# FPGA_A.net
KiCad netlist of a schematic drawn in Altium Designer
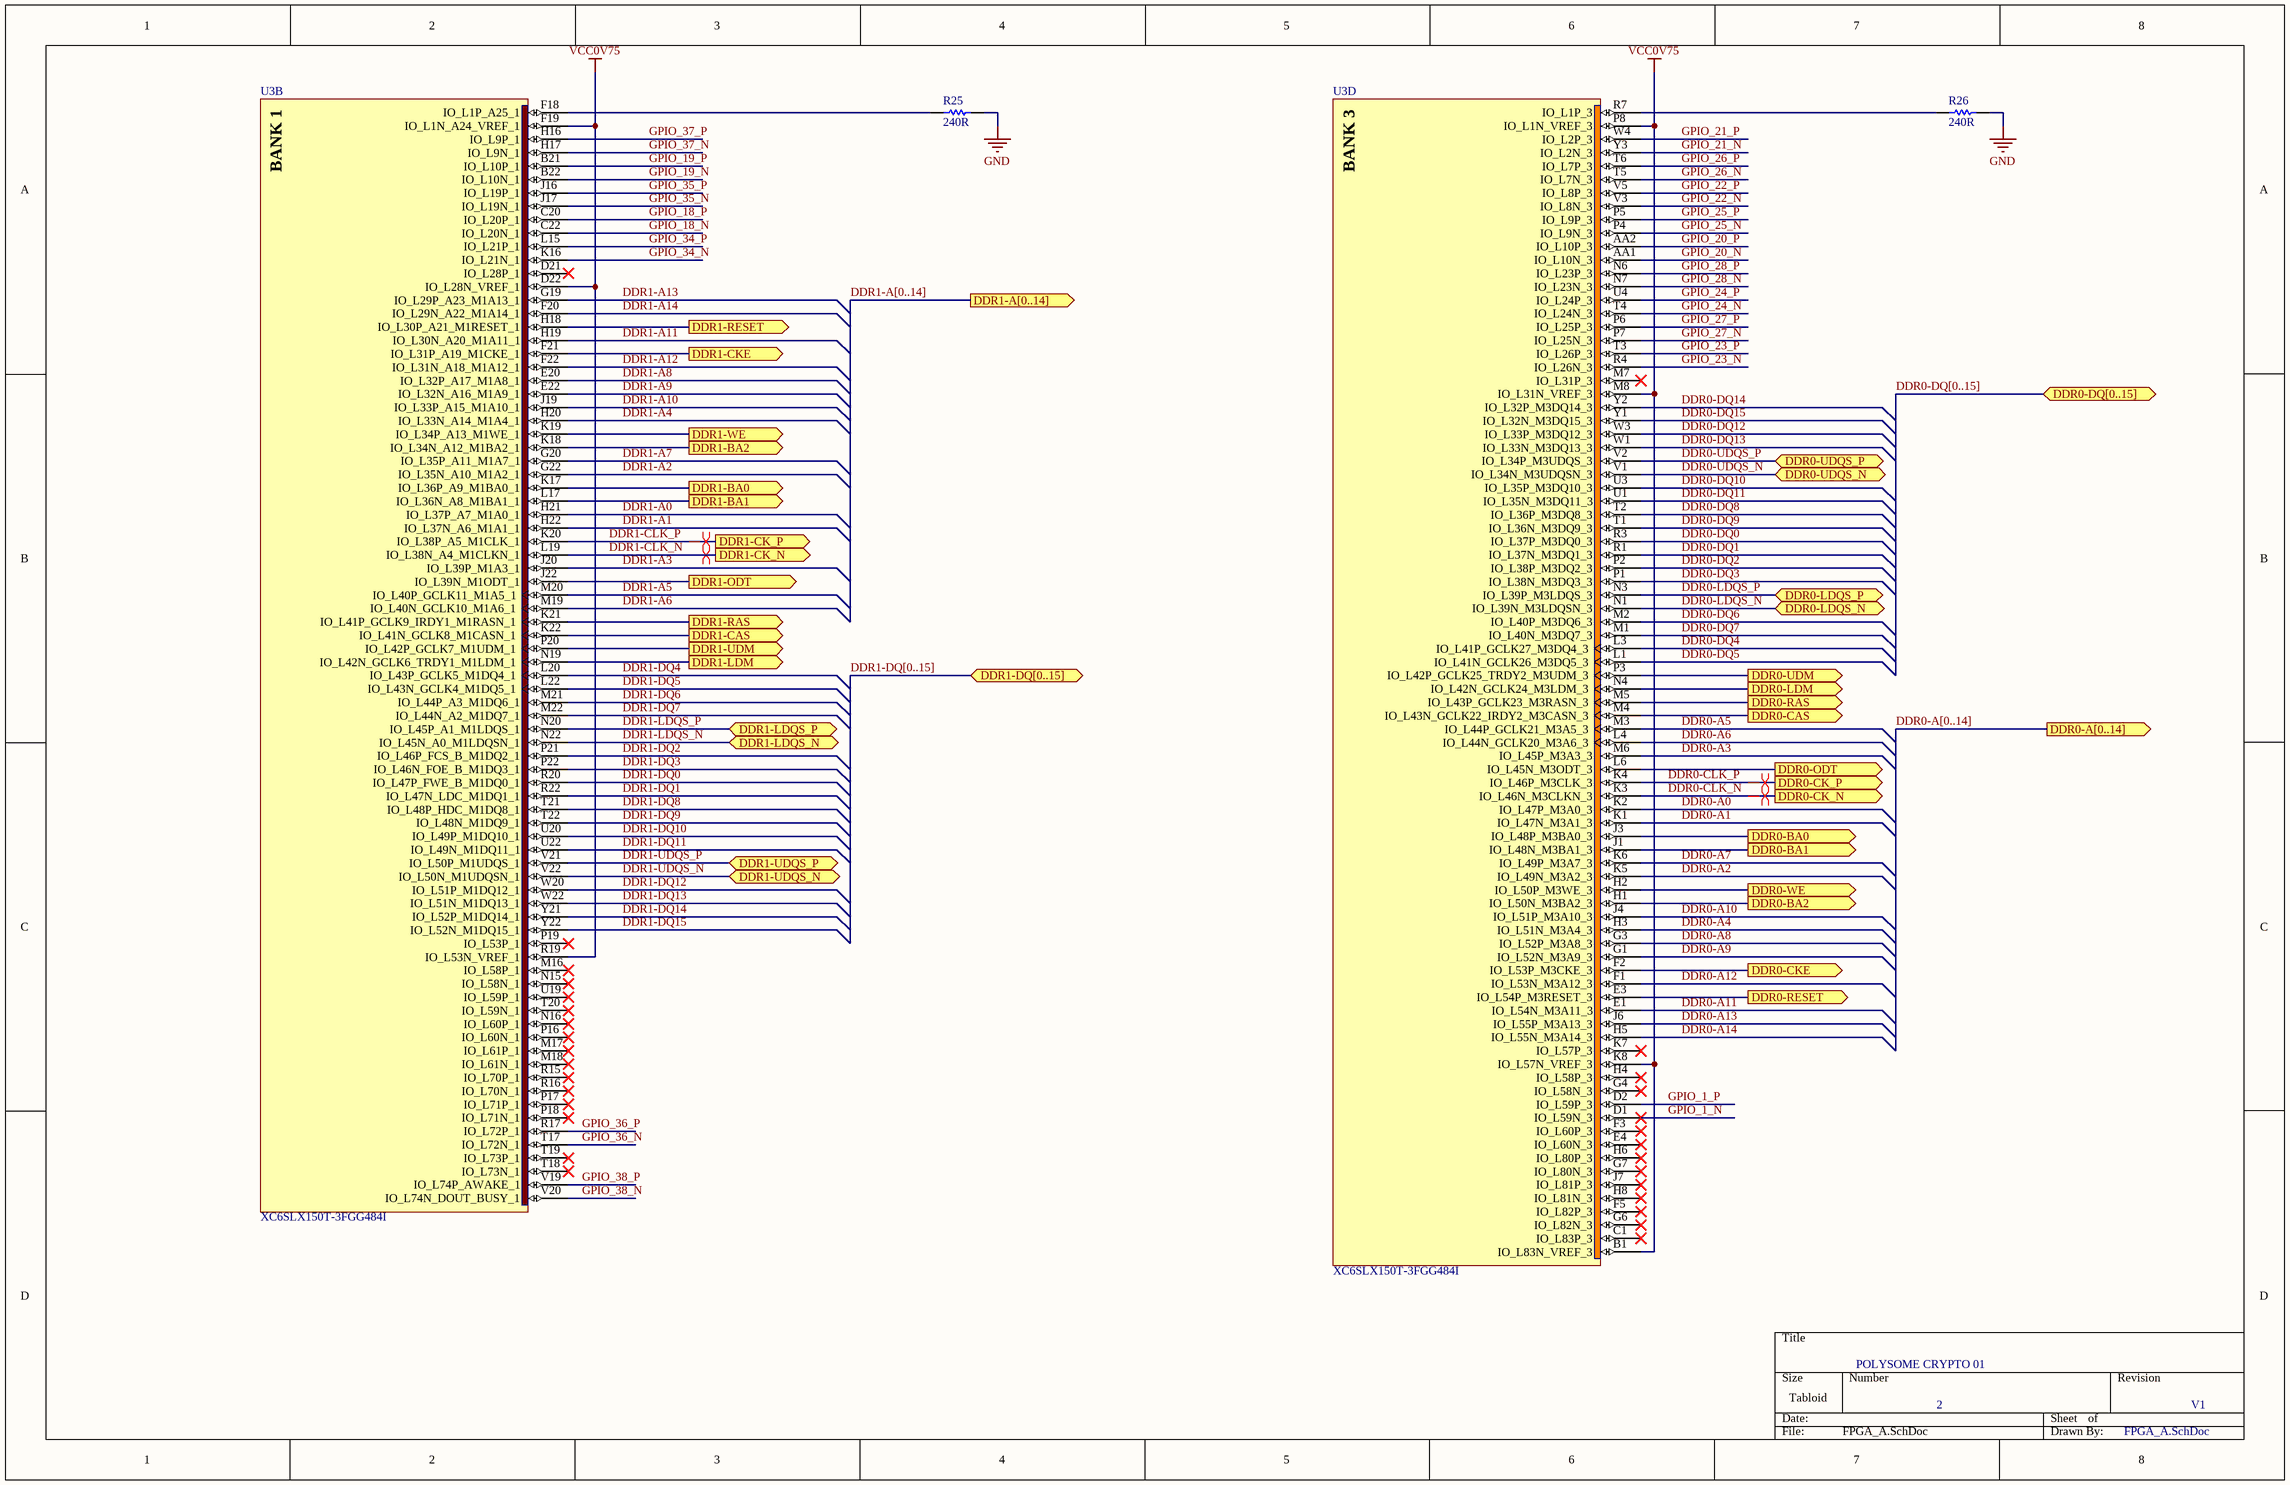
[diagram p0: FPGA_A.SchDoc]

(export (version "E")
  (design (tool "Eeschema 10.0.6"))
  (components
    (comp (ref "R25")
      (value "240R")
      (footprint "0402")
      (description "Semiconductor Resistor")
      (fields (field (name "Comment") "Res Semi") (field (name "PUBLISHER") "Altium Limited"))
      (libsource (lib "Miscellaneous Devices") (part "Res Semi"))
    )
    (comp (ref "R26")
      (value "240R")
      (footprint "0402")
      (description "Semiconductor Resistor")
      (fields (field (name "Comment") "Res Semi") (field (name "PUBLISHER") "Altium Limited"))
      (libsource (lib "Miscellaneous Devices") (part "Res Semi"))
    )
    (comp (ref "U3")
      (value "XC6SLX150T-3FGG484I")
      (footprint "FGG484")
      (fields (field (name "PUBLISHER") "Altium Limited"))
      (libsource (lib "Xilinx Spartan-6") (part "XC6SLX150T-3FGG484I"))
    )
  )
  (nets
    (net (code "1") (name "/DDR0-A0") (class "Default")
      (node (ref "U3") (pin "K2") (pinfunction "IO_L47P_M3A0_3_K2") (pintype "bidirectional"))
    )
    (net (code "2") (name "/DDR0-A1") (class "Default")
      (node (ref "U3") (pin "K1") (pinfunction "IO_L47N_M3A1_3_K1") (pintype "bidirectional"))
    )
    (net (code "3") (name "/DDR0-A2") (class "Default")
      (node (ref "U3") (pin "K5") (pinfunction "IO_L49N_M3A2_3_K5") (pintype "bidirectional"))
    )
    (net (code "4") (name "/DDR0-A3") (class "Default")
      (node (ref "U3") (pin "M6") (pinfunction "IO_L45P_M3A3_3_M6") (pintype "bidirectional"))
    )
    (net (code "5") (name "/DDR0-A4") (class "Default")
      (node (ref "U3") (pin "H3") (pinfunction "IO_L51N_M3A4_3_H3") (pintype "bidirectional"))
    )
    (net (code "6") (name "/DDR0-A5") (class "Default")
      (node (ref "U3") (pin "M3") (pinfunction "IO_L44P_GCLK21_M3A5_3_M3") (pintype "bidirectional"))
    )
    (net (code "7") (name "/DDR0-A6") (class "Default")
      (node (ref "U3") (pin "L4") (pinfunction "IO_L44N_GCLK20_M3A6_3_L4") (pintype "bidirectional"))
    )
    (net (code "8") (name "/DDR0-A7") (class "Default")
      (node (ref "U3") (pin "K6") (pinfunction "IO_L49P_M3A7_3_K6") (pintype "bidirectional"))
    )
    (net (code "9") (name "/DDR0-A8") (class "Default")
      (node (ref "U3") (pin "G3") (pinfunction "IO_L52P_M3A8_3_G3") (pintype "bidirectional"))
    )
    (net (code "10") (name "/DDR0-A9") (class "Default")
      (node (ref "U3") (pin "G1") (pinfunction "IO_L52N_M3A9_3_G1") (pintype "bidirectional"))
    )
    (net (code "11") (name "/DDR0-A10") (class "Default")
      (node (ref "U3") (pin "J4") (pinfunction "IO_L51P_M3A10_3_J4") (pintype "bidirectional"))
    )
    (net (code "12") (name "/DDR0-A11") (class "Default")
      (node (ref "U3") (pin "E1") (pinfunction "IO_L54N_M3A11_3_E1") (pintype "bidirectional"))
    )
    (net (code "13") (name "/DDR0-A12") (class "Default")
      (node (ref "U3") (pin "F1") (pinfunction "IO_L53N_M3A12_3_F1") (pintype "bidirectional"))
    )
    (net (code "14") (name "/DDR0-A13") (class "Default")
      (node (ref "U3") (pin "J6") (pinfunction "IO_L55P_M3A13_3_J6") (pintype "bidirectional"))
    )
    (net (code "15") (name "/DDR0-A14") (class "Default")
      (node (ref "U3") (pin "H5") (pinfunction "IO_L55N_M3A14_3_H5") (pintype "bidirectional"))
    )
    (net (code "17") (name "/DDR0-BA0") (class "Default")
      (node (ref "U3") (pin "J3") (pinfunction "IO_L48P_M3BA0_3_J3") (pintype "bidirectional"))
    )
    (net (code "18") (name "/DDR0-BA1") (class "Default")
      (node (ref "U3") (pin "J1") (pinfunction "IO_L48N_M3BA1_3_J1") (pintype "bidirectional"))
    )
    (net (code "19") (name "/DDR0-BA2") (class "Default")
      (node (ref "U3") (pin "H1") (pinfunction "IO_L50N_M3BA2_3_H1") (pintype "bidirectional"))
    )
    (net (code "20") (name "/DDR0-CAS") (class "Default")
      (node (ref "U3") (pin "M4") (pinfunction "IO_L43N_GCLK22_IRDY2_M3CASN_3_M4") (pintype "bidirectional"))
    )
    (net (code "21") (name "/DDR0-CKE") (class "Default")
      (node (ref "U3") (pin "F2") (pinfunction "IO_L53P_M3CKE_3_F2") (pintype "bidirectional"))
    )
    (net (code "22") (name "/DDR0-CLK_N") (class "Default")
      (node (ref "U3") (pin "K3") (pinfunction "IO_L46N_M3CLKN_3_K3") (pintype "bidirectional"))
    )
    (net (code "23") (name "/DDR0-CLK_P") (class "Default")
      (node (ref "U3") (pin "K4") (pinfunction "IO_L46P_M3CLK_3_K4") (pintype "bidirectional"))
    )
    (net (code "24") (name "/DDR0-DQ0") (class "Default")
      (node (ref "U3") (pin "R3") (pinfunction "IO_L37P_M3DQ0_3_R3") (pintype "bidirectional"))
    )
    (net (code "25") (name "/DDR0-DQ1") (class "Default")
      (node (ref "U3") (pin "R1") (pinfunction "IO_L37N_M3DQ1_3_R1") (pintype "bidirectional"))
    )
    (net (code "26") (name "/DDR0-DQ2") (class "Default")
      (node (ref "U3") (pin "P2") (pinfunction "IO_L38P_M3DQ2_3_P2") (pintype "bidirectional"))
    )
    (net (code "27") (name "/DDR0-DQ3") (class "Default")
      (node (ref "U3") (pin "P1") (pinfunction "IO_L38N_M3DQ3_3_P1") (pintype "bidirectional"))
    )
    (net (code "28") (name "/DDR0-DQ4") (class "Default")
      (node (ref "U3") (pin "L3") (pinfunction "IO_L41P_GCLK27_M3DQ4_3_L3") (pintype "bidirectional"))
    )
    (net (code "29") (name "/DDR0-DQ5") (class "Default")
      (node (ref "U3") (pin "L1") (pinfunction "IO_L41N_GCLK26_M3DQ5_3_L1") (pintype "bidirectional"))
    )
    (net (code "30") (name "/DDR0-DQ6") (class "Default")
      (node (ref "U3") (pin "M2") (pinfunction "IO_L40P_M3DQ6_3_M2") (pintype "bidirectional"))
    )
    (net (code "31") (name "/DDR0-DQ7") (class "Default")
      (node (ref "U3") (pin "M1") (pinfunction "IO_L40N_M3DQ7_3_M1") (pintype "bidirectional"))
    )
    (net (code "32") (name "/DDR0-DQ8") (class "Default")
      (node (ref "U3") (pin "T2") (pinfunction "IO_L36P_M3DQ8_3_T2") (pintype "bidirectional"))
    )
    (net (code "33") (name "/DDR0-DQ9") (class "Default")
      (node (ref "U3") (pin "T1") (pinfunction "IO_L36N_M3DQ9_3_T1") (pintype "bidirectional"))
    )
    (net (code "34") (name "/DDR0-DQ10") (class "Default")
      (node (ref "U3") (pin "U3") (pinfunction "IO_L35P_M3DQ10_3_U3") (pintype "bidirectional"))
    )
    (net (code "35") (name "/DDR0-DQ11") (class "Default")
      (node (ref "U3") (pin "U1") (pinfunction "IO_L35N_M3DQ11_3_U1") (pintype "bidirectional"))
    )
    (net (code "36") (name "/DDR0-DQ12") (class "Default")
      (node (ref "U3") (pin "W3") (pinfunction "IO_L33P_M3DQ12_3_W3") (pintype "bidirectional"))
    )
    (net (code "37") (name "/DDR0-DQ13") (class "Default")
      (node (ref "U3") (pin "W1") (pinfunction "IO_L33N_M3DQ13_3_W1") (pintype "bidirectional"))
    )
    (net (code "38") (name "/DDR0-DQ14") (class "Default")
      (node (ref "U3") (pin "Y2") (pinfunction "IO_L32P_M3DQ14_3_Y2") (pintype "bidirectional"))
    )
    (net (code "39") (name "/DDR0-DQ15") (class "Default")
      (node (ref "U3") (pin "Y1") (pinfunction "IO_L32N_M3DQ15_3_Y1") (pintype "bidirectional"))
    )
    (net (code "41") (name "/DDR0-LDM") (class "Default")
      (node (ref "U3") (pin "N4") (pinfunction "IO_L42N_GCLK24_M3LDM_3_N4") (pintype "bidirectional"))
    )
    (net (code "42") (name "/DDR0-LDQS_N") (class "Default")
      (node (ref "U3") (pin "N1") (pinfunction "IO_L39N_M3LDQSN_3_N1") (pintype "bidirectional"))
    )
    (net (code "43") (name "/DDR0-LDQS_P") (class "Default")
      (node (ref "U3") (pin "N3") (pinfunction "IO_L39P_M3LDQS_3_N3") (pintype "bidirectional"))
    )
    (net (code "44") (name "/DDR0-ODT") (class "Default")
      (node (ref "U3") (pin "L6") (pinfunction "IO_L45N_M3ODT_3_L6") (pintype "bidirectional"))
    )
    (net (code "45") (name "/DDR0-RAS") (class "Default")
      (node (ref "U3") (pin "M5") (pinfunction "IO_L43P_GCLK23_M3RASN_3_M5") (pintype "bidirectional"))
    )
    (net (code "46") (name "/DDR0-RESET") (class "Default")
      (node (ref "U3") (pin "E3") (pinfunction "IO_L54P_M3RESET_3_E3") (pintype "bidirectional"))
    )
    (net (code "47") (name "/DDR0-UDM") (class "Default")
      (node (ref "U3") (pin "P3") (pinfunction "IO_L42P_GCLK25_TRDY2_M3UDM_3_P3") (pintype "bidirectional"))
    )
    (net (code "48") (name "/DDR0-UDQS_N") (class "Default")
      (node (ref "U3") (pin "V1") (pinfunction "IO_L34N_M3UDQSN_3_V1") (pintype "bidirectional"))
    )
    (net (code "49") (name "/DDR0-UDQS_P") (class "Default")
      (node (ref "U3") (pin "V2") (pinfunction "IO_L34P_M3UDQS_3_V2") (pintype "bidirectional"))
    )
    (net (code "50") (name "/DDR0-WE") (class "Default")
      (node (ref "U3") (pin "H2") (pinfunction "IO_L50P_M3WE_3_H2") (pintype "bidirectional"))
    )
    (net (code "51") (name "/DDR1-A0") (class "Default")
      (node (ref "U3") (pin "H21") (pinfunction "IO_L37P_A7_M1A0_1_H21") (pintype "bidirectional"))
    )
    (net (code "52") (name "/DDR1-A1") (class "Default")
      (node (ref "U3") (pin "H22") (pinfunction "IO_L37N_A6_M1A1_1_H22") (pintype "bidirectional"))
    )
    (net (code "53") (name "/DDR1-A2") (class "Default")
      (node (ref "U3") (pin "G22") (pinfunction "IO_L35N_A10_M1A2_1_G22") (pintype "bidirectional"))
    )
    (net (code "54") (name "/DDR1-A3") (class "Default")
      (node (ref "U3") (pin "J20") (pinfunction "IO_L39P_M1A3_1_J20") (pintype "bidirectional"))
    )
    (net (code "55") (name "/DDR1-A4") (class "Default")
      (node (ref "U3") (pin "H20") (pinfunction "IO_L33N_A14_M1A4_1_H20") (pintype "bidirectional"))
    )
    (net (code "56") (name "/DDR1-A5") (class "Default")
      (node (ref "U3") (pin "M20") (pinfunction "IO_L40P_GCLK11_M1A5_1_M20") (pintype "bidirectional"))
    )
    (net (code "57") (name "/DDR1-A6") (class "Default")
      (node (ref "U3") (pin "M19") (pinfunction "IO_L40N_GCLK10_M1A6_1_M19") (pintype "bidirectional"))
    )
    (net (code "58") (name "/DDR1-A7") (class "Default")
      (node (ref "U3") (pin "G20") (pinfunction "IO_L35P_A11_M1A7_1_G20") (pintype "bidirectional"))
    )
    (net (code "59") (name "/DDR1-A8") (class "Default")
      (node (ref "U3") (pin "E20") (pinfunction "IO_L32P_A17_M1A8_1_E20") (pintype "bidirectional"))
    )
    (net (code "60") (name "/DDR1-A9") (class "Default")
      (node (ref "U3") (pin "E22") (pinfunction "IO_L32N_A16_M1A9_1_E22") (pintype "bidirectional"))
    )
    (net (code "61") (name "/DDR1-A10") (class "Default")
      (node (ref "U3") (pin "J19") (pinfunction "IO_L33P_A15_M1A10_1_J19") (pintype "bidirectional"))
    )
    (net (code "62") (name "/DDR1-A11") (class "Default")
      (node (ref "U3") (pin "H19") (pinfunction "IO_L30N_A20_M1A11_1_H19") (pintype "bidirectional"))
    )
    (net (code "63") (name "/DDR1-A12") (class "Default")
      (node (ref "U3") (pin "F22") (pinfunction "IO_L31N_A18_M1A12_1_F22") (pintype "bidirectional"))
    )
    (net (code "64") (name "/DDR1-A13") (class "Default")
      (node (ref "U3") (pin "G19") (pinfunction "IO_L29P_A23_M1A13_1_G19") (pintype "bidirectional"))
    )
    (net (code "65") (name "/DDR1-A14") (class "Default")
      (node (ref "U3") (pin "F20") (pinfunction "IO_L29N_A22_M1A14_1_F20") (pintype "bidirectional"))
    )
    (net (code "67") (name "/DDR1-BA0") (class "Default")
      (node (ref "U3") (pin "K17") (pinfunction "IO_L36P_A9_M1BA0_1_K17") (pintype "bidirectional"))
    )
    (net (code "68") (name "/DDR1-BA1") (class "Default")
      (node (ref "U3") (pin "L17") (pinfunction "IO_L36N_A8_M1BA1_1_L17") (pintype "bidirectional"))
    )
    (net (code "69") (name "/DDR1-BA2") (class "Default")
      (node (ref "U3") (pin "K18") (pinfunction "IO_L34N_A12_M1BA2_1_K18") (pintype "bidirectional"))
    )
    (net (code "70") (name "/DDR1-CAS") (class "Default")
      (node (ref "U3") (pin "K22") (pinfunction "IO_L41N_GCLK8_M1CASN_1_K22") (pintype "bidirectional"))
    )
    (net (code "71") (name "/DDR1-CKE") (class "Default")
      (node (ref "U3") (pin "F21") (pinfunction "IO_L31P_A19_M1CKE_1_F21") (pintype "bidirectional"))
    )
    (net (code "72") (name "/DDR1-CLK_N") (class "Default")
      (node (ref "U3") (pin "L19") (pinfunction "IO_L38N_A4_M1CLKN_1_L19") (pintype "bidirectional"))
    )
    (net (code "73") (name "/DDR1-CLK_P") (class "Default")
      (node (ref "U3") (pin "K20") (pinfunction "IO_L38P_A5_M1CLK_1_K20") (pintype "bidirectional"))
    )
    (net (code "74") (name "/DDR1-DQ0") (class "Default")
      (node (ref "U3") (pin "R20") (pinfunction "IO_L47P_FWE_B_M1DQ0_1_R20") (pintype "bidirectional"))
    )
    (net (code "75") (name "/DDR1-DQ1") (class "Default")
      (node (ref "U3") (pin "R22") (pinfunction "IO_L47N_LDC_M1DQ1_1_R22") (pintype "bidirectional"))
    )
    (net (code "76") (name "/DDR1-DQ2") (class "Default")
      (node (ref "U3") (pin "P21") (pinfunction "IO_L46P_FCS_B_M1DQ2_1_P21") (pintype "bidirectional"))
    )
    (net (code "77") (name "/DDR1-DQ3") (class "Default")
      (node (ref "U3") (pin "P22") (pinfunction "IO_L46N_FOE_B_M1DQ3_1_P22") (pintype "bidirectional"))
    )
    (net (code "78") (name "/DDR1-DQ4") (class "Default")
      (node (ref "U3") (pin "L20") (pinfunction "IO_L43P_GCLK5_M1DQ4_1_L20") (pintype "bidirectional"))
    )
    (net (code "79") (name "/DDR1-DQ5") (class "Default")
      (node (ref "U3") (pin "L22") (pinfunction "IO_L43N_GCLK4_M1DQ5_1_L22") (pintype "bidirectional"))
    )
    (net (code "80") (name "/DDR1-DQ6") (class "Default")
      (node (ref "U3") (pin "M21") (pinfunction "IO_L44P_A3_M1DQ6_1_M21") (pintype "bidirectional"))
    )
    (net (code "81") (name "/DDR1-DQ7") (class "Default")
      (node (ref "U3") (pin "M22") (pinfunction "IO_L44N_A2_M1DQ7_1_M22") (pintype "bidirectional"))
    )
    (net (code "82") (name "/DDR1-DQ8") (class "Default")
      (node (ref "U3") (pin "T21") (pinfunction "IO_L48P_HDC_M1DQ8_1_T21") (pintype "bidirectional"))
    )
    (net (code "83") (name "/DDR1-DQ9") (class "Default")
      (node (ref "U3") (pin "T22") (pinfunction "IO_L48N_M1DQ9_1_T22") (pintype "bidirectional"))
    )
    (net (code "84") (name "/DDR1-DQ10") (class "Default")
      (node (ref "U3") (pin "U20") (pinfunction "IO_L49P_M1DQ10_1_U20") (pintype "bidirectional"))
    )
    (net (code "85") (name "/DDR1-DQ11") (class "Default")
      (node (ref "U3") (pin "U22") (pinfunction "IO_L49N_M1DQ11_1_U22") (pintype "bidirectional"))
    )
    (net (code "86") (name "/DDR1-DQ12") (class "Default")
      (node (ref "U3") (pin "W20") (pinfunction "IO_L51P_M1DQ12_1_W20") (pintype "bidirectional"))
    )
    (net (code "87") (name "/DDR1-DQ13") (class "Default")
      (node (ref "U3") (pin "W22") (pinfunction "IO_L51N_M1DQ13_1_W22") (pintype "bidirectional"))
    )
    (net (code "88") (name "/DDR1-DQ14") (class "Default")
      (node (ref "U3") (pin "Y21") (pinfunction "IO_L52P_M1DQ14_1_Y21") (pintype "bidirectional"))
    )
    (net (code "89") (name "/DDR1-DQ15") (class "Default")
      (node (ref "U3") (pin "Y22") (pinfunction "IO_L52N_M1DQ15_1_Y22") (pintype "bidirectional"))
    )
    (net (code "91") (name "/DDR1-LDM") (class "Default")
      (node (ref "U3") (pin "N19") (pinfunction "IO_L42N_GCLK6_TRDY1_M1LDM_1_N19") (pintype "bidirectional"))
    )
    (net (code "92") (name "/DDR1-LDQS_N") (class "Default")
      (node (ref "U3") (pin "N22") (pinfunction "IO_L45N_A0_M1LDQSN_1_N22") (pintype "bidirectional"))
    )
    (net (code "93") (name "/DDR1-LDQS_P") (class "Default")
      (node (ref "U3") (pin "N20") (pinfunction "IO_L45P_A1_M1LDQS_1_N20") (pintype "bidirectional"))
    )
    (net (code "94") (name "/DDR1-ODT") (class "Default")
      (node (ref "U3") (pin "J22") (pinfunction "IO_L39N_M1ODT_1_J22") (pintype "bidirectional"))
    )
    (net (code "95") (name "/DDR1-RAS") (class "Default")
      (node (ref "U3") (pin "K21") (pinfunction "IO_L41P_GCLK9_IRDY1_M1RASN_1_K21") (pintype "bidirectional"))
    )
    (net (code "96") (name "/DDR1-RESET") (class "Default")
      (node (ref "U3") (pin "H18") (pinfunction "IO_L30P_A21_M1RESET_1_H18") (pintype "bidirectional"))
    )
    (net (code "97") (name "/DDR1-UDM") (class "Default")
      (node (ref "U3") (pin "P20") (pinfunction "IO_L42P_GCLK7_M1UDM_1_P20") (pintype "bidirectional"))
    )
    (net (code "98") (name "/DDR1-UDQS_N") (class "Default")
      (node (ref "U3") (pin "V22") (pinfunction "IO_L50N_M1UDQSN_1_V22") (pintype "bidirectional"))
    )
    (net (code "99") (name "/DDR1-UDQS_P") (class "Default")
      (node (ref "U3") (pin "V21") (pinfunction "IO_L50P_M1UDQS_1_V21") (pintype "bidirectional"))
    )
    (net (code "100") (name "/DDR1-WE") (class "Default")
      (node (ref "U3") (pin "K19") (pinfunction "IO_L34P_A13_M1WE_1_K19") (pintype "bidirectional"))
    )
    (net (code "101") (name "/GPIO_1_N") (class "Default")
      (node (ref "U3") (pin "D1") (pinfunction "IO_L59N_3_D1") (pintype "bidirectional+no_connect"))
    )
    (net (code "102") (name "/GPIO_1_P") (class "Default")
      (node (ref "U3") (pin "D2") (pinfunction "IO_L59P_3_D2") (pintype "bidirectional"))
    )
    (net (code "103") (name "/GPIO_18_N") (class "Default")
      (node (ref "U3") (pin "C22") (pinfunction "IO_L20N_1_C22") (pintype "bidirectional"))
    )
    (net (code "104") (name "/GPIO_18_P") (class "Default")
      (node (ref "U3") (pin "C20") (pinfunction "IO_L20P_1_C20") (pintype "bidirectional"))
    )
    (net (code "105") (name "/GPIO_19_N") (class "Default")
      (node (ref "U3") (pin "B22") (pinfunction "IO_L10N_1_B22") (pintype "bidirectional"))
    )
    (net (code "106") (name "/GPIO_19_P") (class "Default")
      (node (ref "U3") (pin "B21") (pinfunction "IO_L10P_1_B21") (pintype "bidirectional"))
    )
    (net (code "107") (name "/GPIO_20_N") (class "Default")
      (node (ref "U3") (pin "AA1") (pinfunction "IO_L10N_3_AA1") (pintype "bidirectional"))
    )
    (net (code "108") (name "/GPIO_20_P") (class "Default")
      (node (ref "U3") (pin "AA2") (pinfunction "IO_L10P_3_AA2") (pintype "bidirectional"))
    )
    (net (code "109") (name "/GPIO_21_N") (class "Default")
      (node (ref "U3") (pin "Y3") (pinfunction "IO_L2N_3_Y3") (pintype "bidirectional"))
    )
    (net (code "110") (name "/GPIO_21_P") (class "Default")
      (node (ref "U3") (pin "W4") (pinfunction "IO_L2P_3_W4") (pintype "bidirectional"))
    )
    (net (code "111") (name "/GPIO_22_N") (class "Default")
      (node (ref "U3") (pin "V3") (pinfunction "IO_L8N_3_V3") (pintype "bidirectional"))
    )
    (net (code "112") (name "/GPIO_22_P") (class "Default")
      (node (ref "U3") (pin "V5") (pinfunction "IO_L8P_3_V5") (pintype "bidirectional"))
    )
    (net (code "113") (name "/GPIO_23_N") (class "Default")
      (node (ref "U3") (pin "R4") (pinfunction "IO_L26N_3_R4") (pintype "bidirectional"))
    )
    (net (code "114") (name "/GPIO_23_P") (class "Default")
      (node (ref "U3") (pin "T3") (pinfunction "IO_L26P_3_T3") (pintype "bidirectional"))
    )
    (net (code "115") (name "/GPIO_24_N") (class "Default")
      (node (ref "U3") (pin "T4") (pinfunction "IO_L24N_3_T4") (pintype "bidirectional"))
    )
    (net (code "116") (name "/GPIO_24_P") (class "Default")
      (node (ref "U3") (pin "U4") (pinfunction "IO_L24P_3_U4") (pintype "bidirectional"))
    )
    (net (code "117") (name "/GPIO_25_N") (class "Default")
      (node (ref "U3") (pin "P4") (pinfunction "IO_L9N_3_P4") (pintype "bidirectional"))
    )
    (net (code "118") (name "/GPIO_25_P") (class "Default")
      (node (ref "U3") (pin "P5") (pinfunction "IO_L9P_3_P5") (pintype "bidirectional"))
    )
    (net (code "119") (name "/GPIO_26_N") (class "Default")
      (node (ref "U3") (pin "T5") (pinfunction "IO_L7N_3_T5") (pintype "bidirectional"))
    )
    (net (code "120") (name "/GPIO_26_P") (class "Default")
      (node (ref "U3") (pin "T6") (pinfunction "IO_L7P_3_T6") (pintype "bidirectional"))
    )
    (net (code "121") (name "/GPIO_27_N") (class "Default")
      (node (ref "U3") (pin "P7") (pinfunction "IO_L25N_3_P7") (pintype "bidirectional"))
    )
    (net (code "122") (name "/GPIO_27_P") (class "Default")
      (node (ref "U3") (pin "P6") (pinfunction "IO_L25P_3_P6") (pintype "bidirectional"))
    )
    (net (code "123") (name "/GPIO_28_N") (class "Default")
      (node (ref "U3") (pin "N7") (pinfunction "IO_L23N_3_N7") (pintype "bidirectional"))
    )
    (net (code "124") (name "/GPIO_28_P") (class "Default")
      (node (ref "U3") (pin "N6") (pinfunction "IO_L23P_3_N6") (pintype "bidirectional"))
    )
    (net (code "125") (name "/GPIO_34_N") (class "Default")
      (node (ref "U3") (pin "K16") (pinfunction "IO_L21N_1_K16") (pintype "bidirectional"))
    )
    (net (code "126") (name "/GPIO_34_P") (class "Default")
      (node (ref "U3") (pin "L15") (pinfunction "IO_L21P_1_L15") (pintype "bidirectional"))
    )
    (net (code "127") (name "/GPIO_35_N") (class "Default")
      (node (ref "U3") (pin "J17") (pinfunction "IO_L19N_1_J17") (pintype "bidirectional"))
    )
    (net (code "128") (name "/GPIO_35_P") (class "Default")
      (node (ref "U3") (pin "J16") (pinfunction "IO_L19P_1_J16") (pintype "bidirectional"))
    )
    (net (code "129") (name "/GPIO_36_N") (class "Default")
      (node (ref "U3") (pin "T17") (pinfunction "IO_L72N_1_T17") (pintype "bidirectional"))
    )
    (net (code "130") (name "/GPIO_36_P") (class "Default")
      (node (ref "U3") (pin "R17") (pinfunction "IO_L72P_1_R17") (pintype "bidirectional"))
    )
    (net (code "131") (name "/GPIO_37_N") (class "Default")
      (node (ref "U3") (pin "H17") (pinfunction "IO_L9N_1_H17") (pintype "bidirectional"))
    )
    (net (code "132") (name "/GPIO_37_P") (class "Default")
      (node (ref "U3") (pin "H16") (pinfunction "IO_L9P_1_H16") (pintype "bidirectional"))
    )
    (net (code "133") (name "/GPIO_38_N") (class "Default")
      (node (ref "U3") (pin "V20") (pinfunction "IO_L74N_DOUT_BUSY_1_V20") (pintype "bidirectional"))
    )
    (net (code "134") (name "/GPIO_38_P") (class "Default")
      (node (ref "U3") (pin "V19") (pinfunction "IO_L74P_AWAKE_1_V19") (pintype "bidirectional"))
    )
    (net (code "135") (name "GND") (class "Default")
      (node (ref "R25") (pin "2") (pinfunction "2_2") (pintype "passive"))
      (node (ref "R26") (pin "2") (pinfunction "2_2") (pintype "passive"))
    )
    (net (code "136") (name "Net-(U3B-IO_L1P_A25_1)") (class "Default")
      (node (ref "R25") (pin "1") (pinfunction "1_1") (pintype "passive"))
      (node (ref "U3") (pin "F18") (pinfunction "IO_L1P_A25_1_F18") (pintype "bidirectional"))
    )
    (net (code "137") (name "Net-(U3D-IO_L1P_3)") (class "Default")
      (node (ref "R26") (pin "1") (pinfunction "1_1") (pintype "passive"))
      (node (ref "U3") (pin "R7") (pinfunction "IO_L1P_3_R7") (pintype "bidirectional"))
    )
    (net (code "138") (name "VCC0V75") (class "Default")
      (node (ref "U3") (pin "B1") (pinfunction "IO_L83N_VREF_3_B1") (pintype "bidirectional"))
      (node (ref "U3") (pin "D22") (pinfunction "IO_L28N_VREF_1_D22") (pintype "bidirectional"))
      (node (ref "U3") (pin "F19") (pinfunction "IO_L1N_A24_VREF_1_F19") (pintype "bidirectional"))
      (node (ref "U3") (pin "K8") (pinfunction "IO_L57N_VREF_3_K8") (pintype "bidirectional"))
      (node (ref "U3") (pin "M8") (pinfunction "IO_L31N_VREF_3_M8") (pintype "bidirectional"))
      (node (ref "U3") (pin "P8") (pinfunction "IO_L1N_VREF_3_P8") (pintype "bidirectional"))
      (node (ref "U3") (pin "R19") (pinfunction "IO_L53N_VREF_1_R19") (pintype "bidirectional"))
    )
    (net (code "139") (name "unconnected-(U3B-IO_L28P_1-PadD21)") (class "Default")
      (node (ref "U3") (pin "D21") (pinfunction "IO_L28P_1_D21") (pintype "bidirectional+no_connect"))
    )
    (net (code "140") (name "unconnected-(U3B-IO_L53P_1-PadP19)") (class "Default")
      (node (ref "U3") (pin "P19") (pinfunction "IO_L53P_1_P19") (pintype "bidirectional+no_connect"))
    )
    (net (code "141") (name "unconnected-(U3B-IO_L58N_1-PadN15)") (class "Default")
      (node (ref "U3") (pin "N15") (pinfunction "IO_L58N_1_N15") (pintype "bidirectional+no_connect"))
    )
    (net (code "142") (name "unconnected-(U3B-IO_L58P_1-PadM16)") (class "Default")
      (node (ref "U3") (pin "M16") (pinfunction "IO_L58P_1_M16") (pintype "bidirectional+no_connect"))
    )
    (net (code "143") (name "unconnected-(U3B-IO_L59N_1-PadT20)") (class "Default")
      (node (ref "U3") (pin "T20") (pinfunction "IO_L59N_1_T20") (pintype "bidirectional+no_connect"))
    )
    (net (code "144") (name "unconnected-(U3B-IO_L59P_1-PadU19)") (class "Default")
      (node (ref "U3") (pin "U19") (pinfunction "IO_L59P_1_U19") (pintype "bidirectional+no_connect"))
    )
    (net (code "145") (name "unconnected-(U3B-IO_L60N_1-PadP16)") (class "Default")
      (node (ref "U3") (pin "P16") (pinfunction "IO_L60N_1_P16") (pintype "bidirectional+no_connect"))
    )
    (net (code "146") (name "unconnected-(U3B-IO_L60P_1-PadN16)") (class "Default")
      (node (ref "U3") (pin "N16") (pinfunction "IO_L60P_1_N16") (pintype "bidirectional+no_connect"))
    )
    (net (code "147") (name "unconnected-(U3B-IO_L61N_1-PadM18)") (class "Default")
      (node (ref "U3") (pin "M18") (pinfunction "IO_L61N_1_M18") (pintype "bidirectional+no_connect"))
    )
    (net (code "148") (name "unconnected-(U3B-IO_L61P_1-PadM17)") (class "Default")
      (node (ref "U3") (pin "M17") (pinfunction "IO_L61P_1_M17") (pintype "bidirectional+no_connect"))
    )
    (net (code "149") (name "unconnected-(U3B-IO_L70N_1-PadR16)") (class "Default")
      (node (ref "U3") (pin "R16") (pinfunction "IO_L70N_1_R16") (pintype "bidirectional+no_connect"))
    )
    (net (code "150") (name "unconnected-(U3B-IO_L70P_1-PadR15)") (class "Default")
      (node (ref "U3") (pin "R15") (pinfunction "IO_L70P_1_R15") (pintype "bidirectional+no_connect"))
    )
    (net (code "151") (name "unconnected-(U3B-IO_L71N_1-PadP18)") (class "Default")
      (node (ref "U3") (pin "P18") (pinfunction "IO_L71N_1_P18") (pintype "bidirectional+no_connect"))
    )
    (net (code "152") (name "unconnected-(U3B-IO_L71P_1-PadP17)") (class "Default")
      (node (ref "U3") (pin "P17") (pinfunction "IO_L71P_1_P17") (pintype "bidirectional+no_connect"))
    )
    (net (code "153") (name "unconnected-(U3B-IO_L73N_1-PadT18)") (class "Default")
      (node (ref "U3") (pin "T18") (pinfunction "IO_L73N_1_T18") (pintype "bidirectional+no_connect"))
    )
    (net (code "154") (name "unconnected-(U3B-IO_L73P_1-PadT19)") (class "Default")
      (node (ref "U3") (pin "T19") (pinfunction "IO_L73P_1_T19") (pintype "bidirectional+no_connect"))
    )
    (net (code "155") (name "unconnected-(U3D-IO_L31P_3-PadM7)") (class "Default")
      (node (ref "U3") (pin "M7") (pinfunction "IO_L31P_3_M7") (pintype "bidirectional+no_connect"))
    )
    (net (code "156") (name "unconnected-(U3D-IO_L57P_3-PadK7)") (class "Default")
      (node (ref "U3") (pin "K7") (pinfunction "IO_L57P_3_K7") (pintype "bidirectional+no_connect"))
    )
    (net (code "157") (name "unconnected-(U3D-IO_L58N_3-PadG4)") (class "Default")
      (node (ref "U3") (pin "G4") (pinfunction "IO_L58N_3_G4") (pintype "bidirectional+no_connect"))
    )
    (net (code "158") (name "unconnected-(U3D-IO_L58P_3-PadH4)") (class "Default")
      (node (ref "U3") (pin "H4") (pinfunction "IO_L58P_3_H4") (pintype "bidirectional+no_connect"))
    )
    (net (code "159") (name "unconnected-(U3D-IO_L60N_3-PadE4)") (class "Default")
      (node (ref "U3") (pin "E4") (pinfunction "IO_L60N_3_E4") (pintype "bidirectional+no_connect"))
    )
    (net (code "160") (name "unconnected-(U3D-IO_L60P_3-PadF3)") (class "Default")
      (node (ref "U3") (pin "F3") (pinfunction "IO_L60P_3_F3") (pintype "bidirectional+no_connect"))
    )
    (net (code "161") (name "unconnected-(U3D-IO_L80N_3-PadG7)") (class "Default")
      (node (ref "U3") (pin "G7") (pinfunction "IO_L80N_3_G7") (pintype "bidirectional+no_connect"))
    )
    (net (code "162") (name "unconnected-(U3D-IO_L80P_3-PadH6)") (class "Default")
      (node (ref "U3") (pin "H6") (pinfunction "IO_L80P_3_H6") (pintype "bidirectional+no_connect"))
    )
    (net (code "163") (name "unconnected-(U3D-IO_L81N_3-PadH8)") (class "Default")
      (node (ref "U3") (pin "H8") (pinfunction "IO_L81N_3_H8") (pintype "bidirectional+no_connect"))
    )
    (net (code "164") (name "unconnected-(U3D-IO_L81P_3-PadJ7)") (class "Default")
      (node (ref "U3") (pin "J7") (pinfunction "IO_L81P_3_J7") (pintype "bidirectional+no_connect"))
    )
    (net (code "165") (name "unconnected-(U3D-IO_L82N_3-PadG6)") (class "Default")
      (node (ref "U3") (pin "G6") (pinfunction "IO_L82N_3_G6") (pintype "bidirectional+no_connect"))
    )
    (net (code "166") (name "unconnected-(U3D-IO_L82P_3-PadF5)") (class "Default")
      (node (ref "U3") (pin "F5") (pinfunction "IO_L82P_3_F5") (pintype "bidirectional+no_connect"))
    )
    (net (code "167") (name "unconnected-(U3D-IO_L83P_3-PadC1)") (class "Default")
      (node (ref "U3") (pin "C1") (pinfunction "IO_L83P_3_C1") (pintype "bidirectional+no_connect"))
    )
  )
)
